# Nano_1.net
KiCad netlist of a schematic drawn in EAGLE
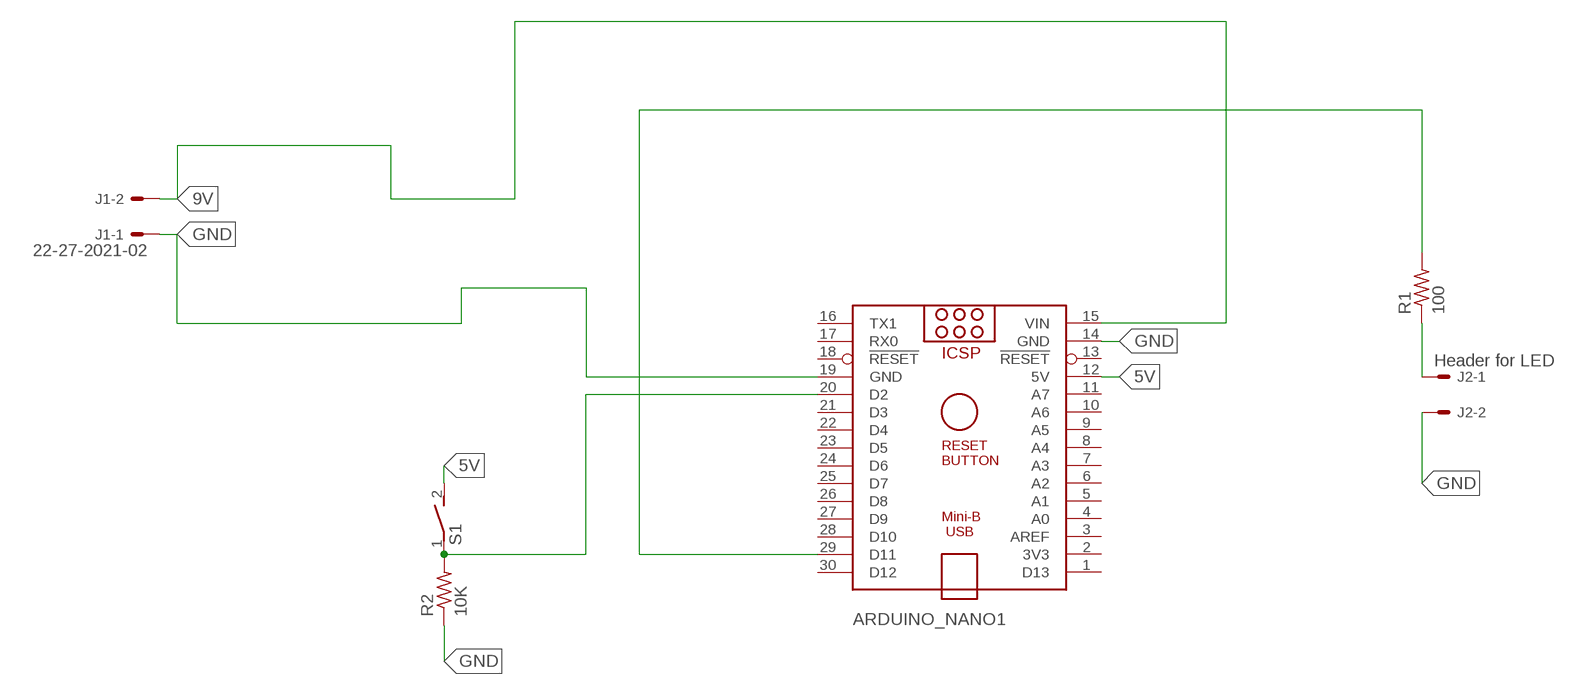
[diagram p0: schematic, sheet 1]

(export (version "E")
  (design (tool "Eeschema 10.0.6"))
  (components
    (comp (ref "ARDUINO_NANO1")
      (value "ARDUINO_NANO")
      (footprint "eagle-import:ARDUINO_NANO")
      (libsource (lib "eagle-import") (part "ARDUINO_NANO"))
    )
    (comp (ref "J1")
      (value "22-27-2021-02")
      (footprint "eagle-import:6410-02")
      (fields (field (name "MF") "MOLEX"))
      (libsource (lib "eagle-import") (part "22-?-0227-2021"))
    )
    (comp (ref "J2")
      (value "Header for LED")
      (footprint "eagle-import:6410-02")
      (fields (field (name "MF") "MOLEX"))
      (libsource (lib "eagle-import") (part "22-?-0227-2021"))
    )
    (comp (ref "R1")
      (value "100")
      (footprint "eagle-import:0207_12")
      (libsource (lib "eagle-import") (part "R-US_0207/12"))
    )
    (comp (ref "R2")
      (value "10K")
      (footprint "eagle-import:0207_12")
      (libsource (lib "eagle-import") (part "R-US_0207/12"))
    )
    (comp (ref "S1")
      (value "DS01E")
      (footprint "eagle-import:DS-01")
      (libsource (lib "eagle-import") (part "DS01E"))
    )
  )
  (nets
    (net (code "1") (name "5V") (class "Default")
      (node (ref "ARDUINO_NANO1") (pin "12") (pinfunction "5V_12") (pintype "power_in"))
      (node (ref "S1") (pin "2") (pinfunction "2_2") (pintype "passive"))
    )
    (net (code "2") (name "9V") (class "Default")
      (node (ref "ARDUINO_NANO1") (pin "15") (pinfunction "VIN_15") (pintype "power_in"))
      (node (ref "J1") (pin "2") (pinfunction "S_2") (pintype "passive"))
    )
    (net (code "3") (name "GND") (class "Default")
      (node (ref "ARDUINO_NANO1") (pin "14") (pinfunction "GND_14") (pintype "power_in"))
      (node (ref "ARDUINO_NANO1") (pin "19") (pinfunction "GND_19") (pintype "power_in"))
      (node (ref "J1") (pin "1") (pinfunction "S_1") (pintype "passive"))
      (node (ref "J2") (pin "2") (pinfunction "S_2") (pintype "passive"))
      (node (ref "R2") (pin "1") (pinfunction "1_1") (pintype "passive"))
    )
    (net (code "4") (name "Net-(ARDUINO_NANO1-D2)") (class "Default")
      (node (ref "ARDUINO_NANO1") (pin "20") (pinfunction "D2_20") (pintype "bidirectional"))
      (node (ref "R2") (pin "2") (pinfunction "2_2") (pintype "passive"))
      (node (ref "S1") (pin "1") (pinfunction "1_1") (pintype "passive"))
    )
    (net (code "5") (name "Net-(ARDUINO_NANO1-D11)") (class "Default")
      (node (ref "ARDUINO_NANO1") (pin "29") (pinfunction "D11_29") (pintype "bidirectional"))
      (node (ref "R1") (pin "2") (pinfunction "2_2") (pintype "passive"))
    )
    (net (code "6") (name "Net-(J2A-S)") (class "Default")
      (node (ref "J2") (pin "1") (pinfunction "S_1") (pintype "passive"))
      (node (ref "R1") (pin "1") (pinfunction "1_1") (pintype "passive"))
    )
    (net (code "7") (name "unconnected-(ARDUINO_NANO1-3V3-Pad2)") (class "Default")
      (node (ref "ARDUINO_NANO1") (pin "2") (pinfunction "3V3_2") (pintype "output"))
    )
    (net (code "8") (name "unconnected-(ARDUINO_NANO1-A0-Pad4)") (class "Default")
      (node (ref "ARDUINO_NANO1") (pin "4") (pinfunction "A0_4") (pintype "bidirectional"))
    )
    (net (code "9") (name "unconnected-(ARDUINO_NANO1-A1-Pad5)") (class "Default")
      (node (ref "ARDUINO_NANO1") (pin "5") (pinfunction "A1_5") (pintype "bidirectional"))
    )
    (net (code "10") (name "unconnected-(ARDUINO_NANO1-A2-Pad6)") (class "Default")
      (node (ref "ARDUINO_NANO1") (pin "6") (pinfunction "A2_6") (pintype "bidirectional"))
    )
    (net (code "11") (name "unconnected-(ARDUINO_NANO1-A3-Pad7)") (class "Default")
      (node (ref "ARDUINO_NANO1") (pin "7") (pinfunction "A3_7") (pintype "bidirectional"))
    )
    (net (code "12") (name "unconnected-(ARDUINO_NANO1-A4-Pad8)") (class "Default")
      (node (ref "ARDUINO_NANO1") (pin "8") (pinfunction "A4_8") (pintype "bidirectional"))
    )
    (net (code "13") (name "unconnected-(ARDUINO_NANO1-A5-Pad9)") (class "Default")
      (node (ref "ARDUINO_NANO1") (pin "9") (pinfunction "A5_9") (pintype "bidirectional"))
    )
    (net (code "14") (name "unconnected-(ARDUINO_NANO1-A6-Pad10)") (class "Default")
      (node (ref "ARDUINO_NANO1") (pin "10") (pinfunction "A6_10") (pintype "bidirectional"))
    )
    (net (code "15") (name "unconnected-(ARDUINO_NANO1-A7-Pad11)") (class "Default")
      (node (ref "ARDUINO_NANO1") (pin "11") (pinfunction "A7_11") (pintype "bidirectional"))
    )
    (net (code "16") (name "unconnected-(ARDUINO_NANO1-AREF-Pad3)") (class "Default")
      (node (ref "ARDUINO_NANO1") (pin "3") (pinfunction "AREF_3") (pintype "input"))
    )
    (net (code "17") (name "unconnected-(ARDUINO_NANO1-D3-Pad21)") (class "Default")
      (node (ref "ARDUINO_NANO1") (pin "21") (pinfunction "D3_21") (pintype "bidirectional"))
    )
    (net (code "18") (name "unconnected-(ARDUINO_NANO1-D4-Pad22)") (class "Default")
      (node (ref "ARDUINO_NANO1") (pin "22") (pinfunction "D4_22") (pintype "bidirectional"))
    )
    (net (code "19") (name "unconnected-(ARDUINO_NANO1-D5-Pad23)") (class "Default")
      (node (ref "ARDUINO_NANO1") (pin "23") (pinfunction "D5_23") (pintype "bidirectional"))
    )
    (net (code "20") (name "unconnected-(ARDUINO_NANO1-D6-Pad24)") (class "Default")
      (node (ref "ARDUINO_NANO1") (pin "24") (pinfunction "D6_24") (pintype "bidirectional"))
    )
    (net (code "21") (name "unconnected-(ARDUINO_NANO1-D7-Pad25)") (class "Default")
      (node (ref "ARDUINO_NANO1") (pin "25") (pinfunction "D7_25") (pintype "bidirectional"))
    )
    (net (code "22") (name "unconnected-(ARDUINO_NANO1-D8-Pad26)") (class "Default")
      (node (ref "ARDUINO_NANO1") (pin "26") (pinfunction "D8_26") (pintype "bidirectional"))
    )
    (net (code "23") (name "unconnected-(ARDUINO_NANO1-D9-Pad27)") (class "Default")
      (node (ref "ARDUINO_NANO1") (pin "27") (pinfunction "D9_27") (pintype "bidirectional"))
    )
    (net (code "24") (name "unconnected-(ARDUINO_NANO1-D10-Pad28)") (class "Default")
      (node (ref "ARDUINO_NANO1") (pin "28") (pinfunction "D10_28") (pintype "bidirectional"))
    )
    (net (code "25") (name "unconnected-(ARDUINO_NANO1-D12-Pad30)") (class "Default")
      (node (ref "ARDUINO_NANO1") (pin "30") (pinfunction "D12_30") (pintype "bidirectional"))
    )
    (net (code "26") (name "unconnected-(ARDUINO_NANO1-D13-Pad1)") (class "Default")
      (node (ref "ARDUINO_NANO1") (pin "1") (pinfunction "D13_1") (pintype "bidirectional"))
    )
    (net (code "27") (name "unconnected-(ARDUINO_NANO1-RX0-Pad17)") (class "Default")
      (node (ref "ARDUINO_NANO1") (pin "17") (pinfunction "RX0_17") (pintype "bidirectional"))
    )
    (net (code "28") (name "unconnected-(ARDUINO_NANO1-TX1-Pad16)") (class "Default")
      (node (ref "ARDUINO_NANO1") (pin "16") (pinfunction "TX1_16") (pintype "bidirectional"))
    )
    (net (code "29") (name "unconnected-(ARDUINO_NANO1-~{RESET}-Pad13)") (class "Default")
      (node (ref "ARDUINO_NANO1") (pin "13") (pinfunction "~{RESET}_13") (pintype "input"))
    )
    (net (code "30") (name "unconnected-(ARDUINO_NANO1-~{RESET}-Pad18)") (class "Default")
      (node (ref "ARDUINO_NANO1") (pin "18") (pinfunction "~{RESET}_18") (pintype "input"))
    )
  )
)
